# BMS-S04-V00-Microcontroller.net
KiCad netlist of a schematic drawn in Altium Designer
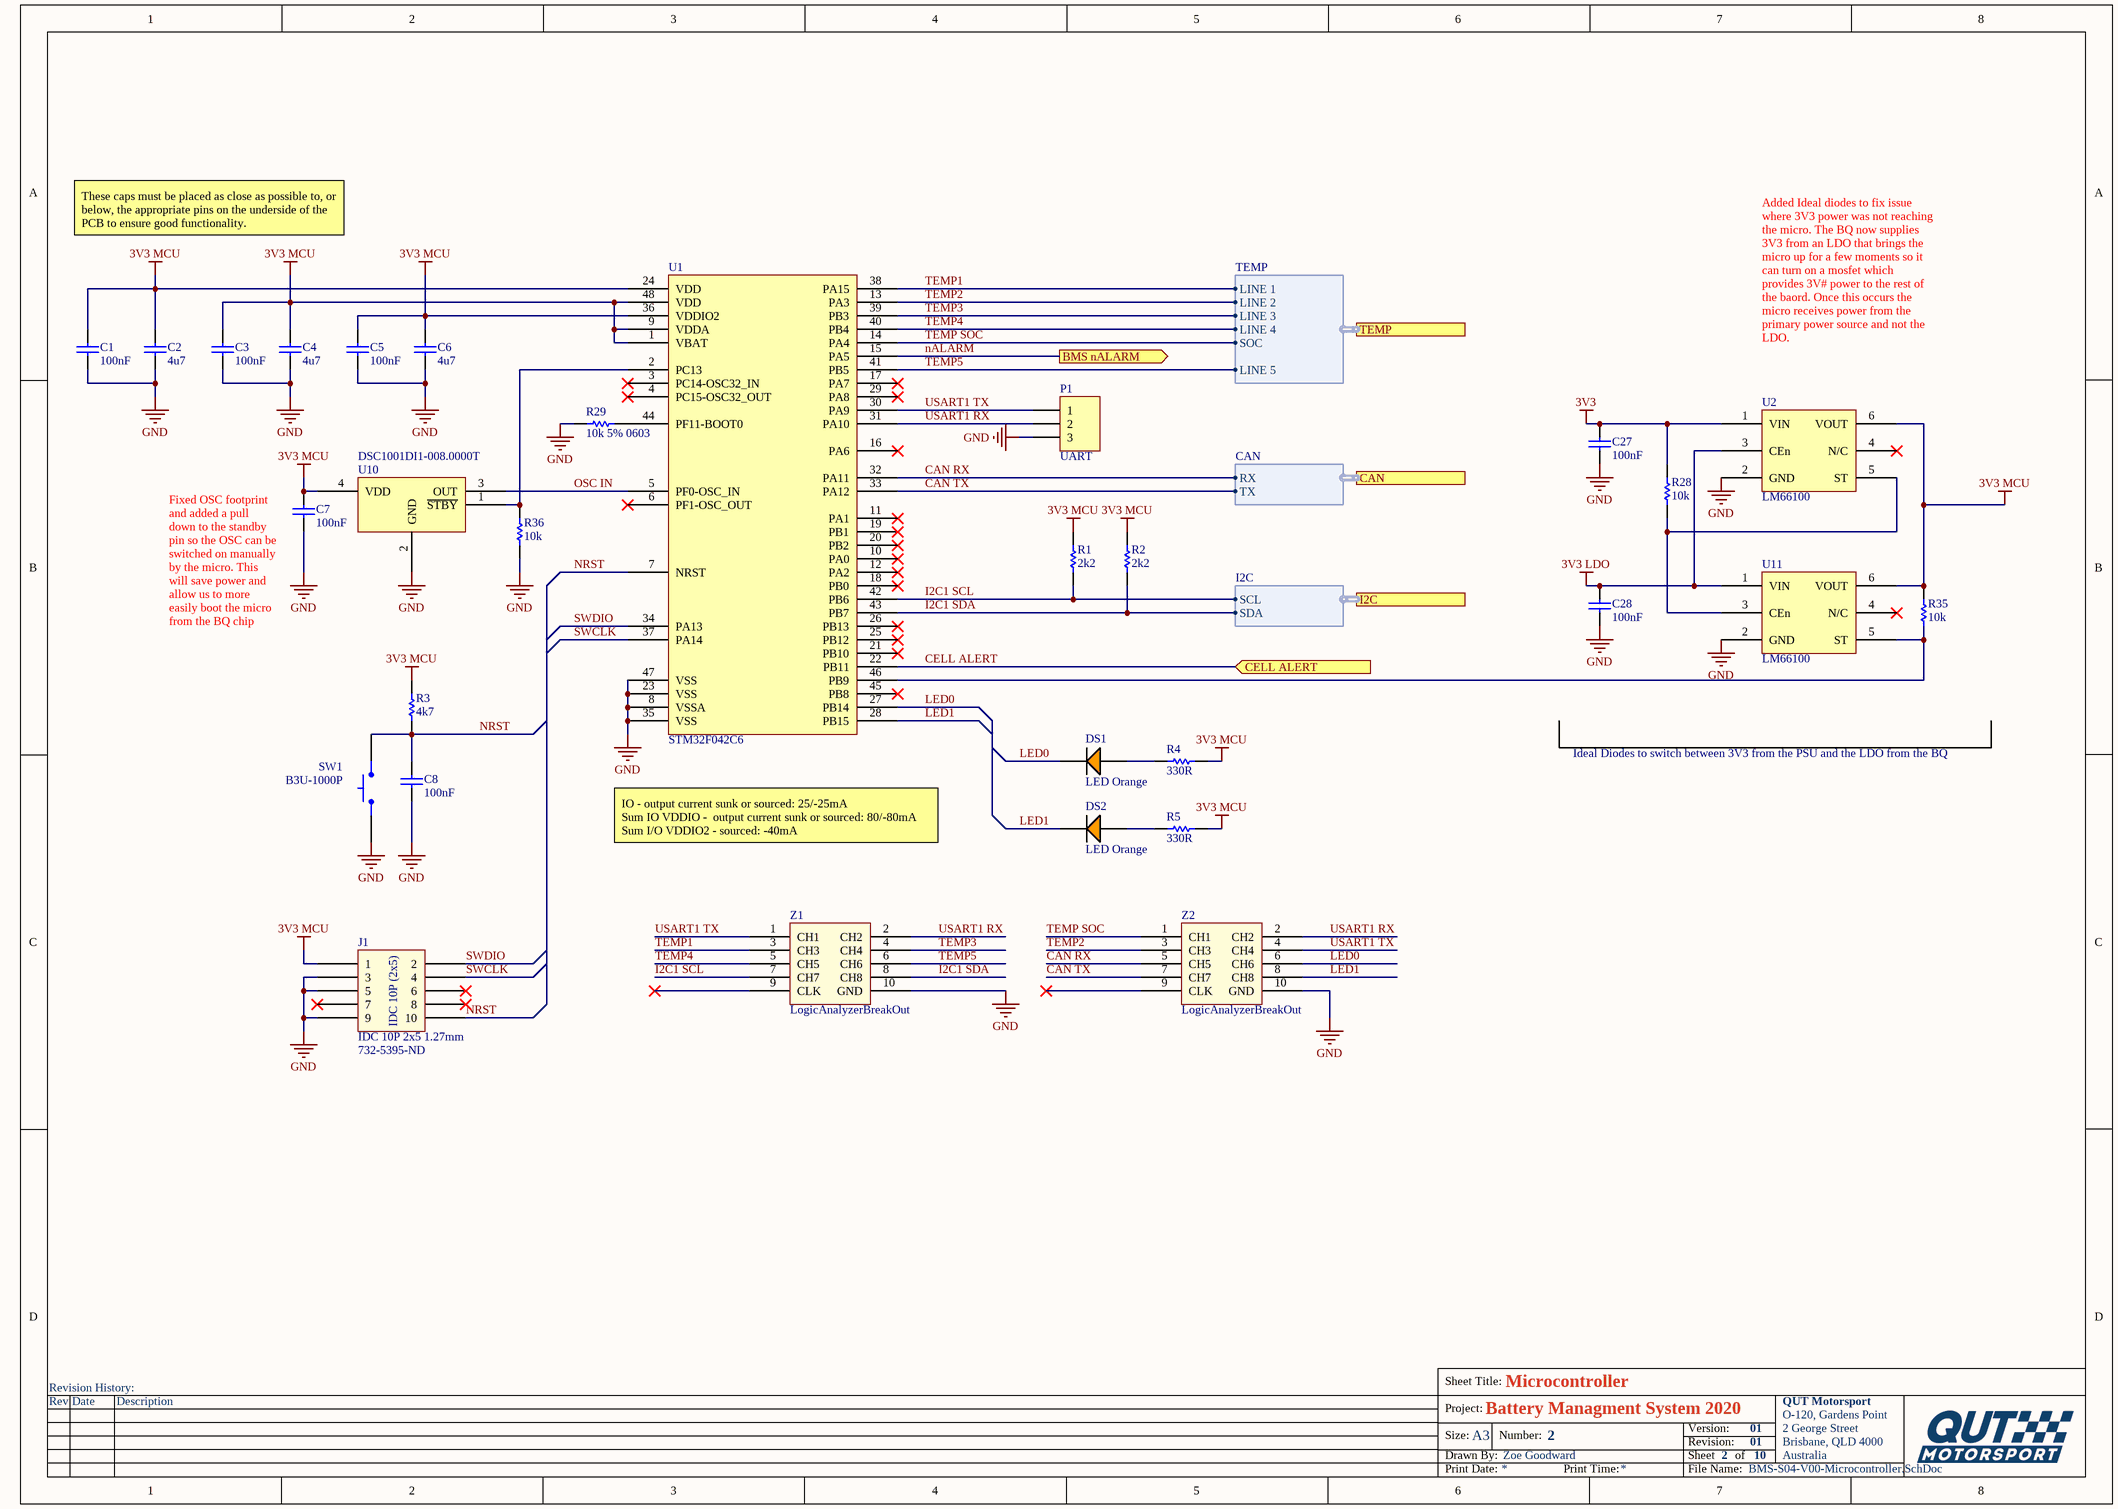
[diagram p0: BMS-S04-V00-Microcontroller.SchDoc]

(export (version "E")
  (design (tool "Eeschema 10.0.6"))
  (components
    (comp (ref "C1")
      (value "100nF")
      (footprint "Cap_Ceramic_0603")
      (description "Capacitor, Ceramic, SMD, 100nF, 50V, 5%, X7R, 0603")
      (libsource (lib "StandardCapacitors") (part "100nF 50V 5% X7R 0603"))
    )
    (comp (ref "C2")
      (value "4u7")
      (footprint "Cap_Ceramic_0603")
      (description "Capacitor, Ceramic, SMD, 4u7, 50V, 5%, X7R, 0603")
      (libsource (lib "StandardCapacitors") (part "4u7 50V 5% X7R 0603"))
    )
    (comp (ref "C3")
      (value "100nF")
      (footprint "Cap_Ceramic_0603")
      (description "Capacitor, Ceramic, SMD, 100nF, 50V, 5%, X7R, 0603")
      (libsource (lib "StandardCapacitors") (part "100nF 50V 5% X7R 0603"))
    )
    (comp (ref "C4")
      (value "4u7")
      (footprint "Cap_Ceramic_0603")
      (description "Capacitor, Ceramic, SMD, 4u7, 50V, 5%, X7R, 0603")
      (libsource (lib "StandardCapacitors") (part "4u7 50V 5% X7R 0603"))
    )
    (comp (ref "C5")
      (value "100nF")
      (footprint "Cap_Ceramic_0603")
      (description "Capacitor, Ceramic, SMD, 100nF, 50V, 5%, X7R, 0603")
      (libsource (lib "StandardCapacitors") (part "100nF 50V 5% X7R 0603"))
    )
    (comp (ref "C6")
      (value "4u7")
      (footprint "Cap_Ceramic_0603")
      (description "Capacitor, Ceramic, SMD, 4u7, 50V, 5%, X7R, 0603")
      (libsource (lib "StandardCapacitors") (part "4u7 50V 5% X7R 0603"))
    )
    (comp (ref "C7")
      (value "100nF")
      (footprint "Cap_Ceramic_0603")
      (description "Capacitor, Ceramic, SMD, 100nF, 50V, 5%, X7R, 0603")
      (libsource (lib "StandardCapacitors") (part "100nF 50V 5% X7R 0603"))
    )
    (comp (ref "C8")
      (value "100nF")
      (footprint "Cap_Ceramic_0603")
      (description "Capacitor, Ceramic, SMD, 100nF, 50V, 5%, X7R, 0603")
      (libsource (lib "StandardCapacitors") (part "100nF 50V 5% X7R 0603"))
    )
    (comp (ref "C27")
      (value "100nF")
      (footprint "Cap_Ceramic_0603")
      (description "Capacitor, Ceramic, SMD, 100nF, 50V, 5%, X7R, 0603")
      (libsource (lib "StandardCapacitors") (part "100nF 50V 5% X7R 0603"))
    )
    (comp (ref "C28")
      (value "100nF")
      (footprint "Cap_Ceramic_0603")
      (description "Capacitor, Ceramic, SMD, 100nF, 50V, 5%, X7R, 0603")
      (libsource (lib "StandardCapacitors") (part "100nF 50V 5% X7R 0603"))
    )
    (comp (ref "DS1")
      (value "LED Orange")
      (footprint "LED ORANGE 0603")
      (libsource (lib "QUTMS_LEDLibrary") (part "LED ORANGE 0603"))
    )
    (comp (ref "DS2")
      (value "LED Orange")
      (footprint "LED ORANGE 0603")
      (libsource (lib "QUTMS_LEDLibrary") (part "LED ORANGE 0603"))
    )
    (comp (ref "J1")
      (value "IDC 10P 2x5 1.27mm")
      (footprint "IDC 1.27MM 10P")
      (libsource (lib "IDCConnectors") (part "IDC 10P 2x5 1.27mm"))
    )
    (comp (ref "P1")
      (value "UART")
      (footprint "HDR1X3")
      (description "Header, 3-Pin")
      (fields (field (name "PUBLISHER") "Altium Limited"))
      (libsource (lib "Miscellaneous Connectors") (part "Header 3"))
    )
    (comp (ref "R1")
      (value "2k2")
      (footprint "Res_ThinFilm_0603")
      (description "Resistor, SMD, 2k2, 0.1W, 5%, 0603")
      (libsource (lib "StandardResistors") (part "2k2 5% 0603"))
    )
    (comp (ref "R2")
      (value "2k2")
      (footprint "Res_ThinFilm_0603")
      (description "Resistor, SMD, 2k2, 0.1W, 5%, 0603")
      (libsource (lib "StandardResistors") (part "2k2 5% 0603"))
    )
    (comp (ref "R3")
      (value "4k7")
      (footprint "Res_ThinFilm_0603")
      (description "Resistor, SMD, 4k7, 0.1W, 5%, 0603")
      (libsource (lib "StandardResistors") (part "4k7 5% 0603"))
    )
    (comp (ref "R4")
      (value "330R")
      (footprint "Res_ThinFilm_0603")
      (description "Resistor, SMD, 330R, 0.1W, 5%, 0603")
      (libsource (lib "StandardResistors") (part "330R 5% 0603"))
    )
    (comp (ref "R5")
      (value "330R")
      (footprint "Res_ThinFilm_0603")
      (description "Resistor, SMD, 330R, 0.1W, 5%, 0603")
      (libsource (lib "StandardResistors") (part "330R 5% 0603"))
    )
    (comp (ref "R28")
      (value "10k")
      (footprint "Res_ThinFilm_0603")
      (description "Resistor, SMD, 10k, 0.1W, 1%, 0603")
      (libsource (lib "StandardResistors") (part "10k 1% 0603"))
    )
    (comp (ref "R29")
      (value "10k 5% 0603")
      (footprint "Res_ThinFilm_0603")
      (description "Resistor, SMD, 10k, 0.1W, 5%, 0603")
      (libsource (lib "StandardResistors") (part "10k 5% 0603"))
    )
    (comp (ref "R35")
      (value "10k")
      (footprint "Res_ThinFilm_0603")
      (description "Resistor, SMD, 10k, 0.1W, 1%, 0603")
      (libsource (lib "StandardResistors") (part "10k 1% 0603"))
    )
    (comp (ref "R36")
      (value "10k")
      (footprint "Res_ThinFilm_0603")
      (description "Resistor, SMD, 10k, 0.1W, 5%, 0603")
      (libsource (lib "StandardResistors") (part "10k 5% 0603"))
    )
    (comp (ref "SW1")
      (value "B3U-1000P")
      (footprint "BTN B3U-1000P")
      (description "Omron B3U-1000P Ultra Miniture Switch")
      (libsource (lib "QUTMS_SwitchLibrary") (part "BTN B3U-1000P"))
    )
    (comp (ref "U1")
      (value "STM32F042C6")
      (footprint "STM32F042C6")
      (description "ARM® Cortex®-M0 STM32F0 Microcontroller IC 32-Bit 48MHz 32KB (32K x 8) FLASH 48-LQFP (7x7)")
      (libsource (lib "QUTMS_STM32Library") (part "STM32042C6"))
    )
    (comp (ref "U2")
      (value "LM66100")
      (footprint "LM66100")
      (description "Diode, SMD, 5.5V, 1.5A, SC-70")
      (fields
        (field (name "MANUFACTURER") "ON Semiconductor / Fairchild")
        (field (name "MANUFACTURER PART NUMBER") "1N914BWS")
      )
      (libsource (lib "QUTMS_DiodeLibrary") (part "LM66100"))
    )
    (comp (ref "U10")
      (value "DSC1001DI1-008.0000T")
      (footprint "DSC1001DI1-008.0000TCT-ND")
      (description "8MHz XO (Standard) CMOS Oscillator 1.8 ~ 3.3V Standby (Power Down) 4-SMD, No Lead")
      (libsource (lib "QUTMS_CrystalLibrary") (part "DSC1001DI1-008.0000T"))
    )
    (comp (ref "U11")
      (value "LM66100")
      (footprint "LM66100")
      (description "Diode, SMD, 5.5V, 1.5A, SC-70")
      (fields
        (field (name "MANUFACTURER") "ON Semiconductor / Fairchild")
        (field (name "MANUFACTURER PART NUMBER") "1N914BWS")
      )
      (libsource (lib "QUTMS_DiodeLibrary") (part "LM66100"))
    )
    (comp (ref "Z1")
      (value "LogicAnalyzerBreakOut")
      (footprint "LogicAnalyzer")
      (libsource (lib "StandardTest") (part "LogicAnalyer"))
    )
    (comp (ref "Z2")
      (value "LogicAnalyzerBreakOut")
      (footprint "LogicAnalyzer")
      (libsource (lib "StandardTest") (part "LogicAnalyer"))
    )
  )
  (nets
    (net (code "4") (name "/CAN RX") (class "Default")
      (node (ref "U1") (pin "32") (pinfunction "PA11_32") (pintype "passive"))
      (node (ref "Z2") (pin "5") (pinfunction "CH5_5") (pintype "passive"))
    )
    (net (code "5") (name "/CAN TX") (class "Default")
      (node (ref "U1") (pin "33") (pinfunction "PA12_33") (pintype "passive"))
      (node (ref "Z2") (pin "7") (pinfunction "CH7_7") (pintype "passive"))
    )
    (net (code "6") (name "/CELL ALERT") (class "Default")
      (node (ref "U1") (pin "22") (pinfunction "PB11_22") (pintype "passive"))
    )
    (net (code "7") (name "/I2C1 SCL") (class "Default")
      (node (ref "R1") (pin "1") (pinfunction "1_1") (pintype "passive"))
      (node (ref "U1") (pin "42") (pinfunction "PB6_42") (pintype "passive"))
      (node (ref "Z1") (pin "7") (pinfunction "CH7_7") (pintype "passive"))
    )
    (net (code "8") (name "/I2C1 SDA") (class "Default")
      (node (ref "R2") (pin "1") (pinfunction "1_1") (pintype "passive"))
      (node (ref "U1") (pin "43") (pinfunction "PB7_43") (pintype "passive"))
      (node (ref "Z1") (pin "8") (pinfunction "CH8_8") (pintype "passive"))
    )
    (net (code "9") (name "/LED0") (class "Default")
      (node (ref "DS1") (pin "2") (pinfunction "C_2") (pintype "passive"))
      (node (ref "U1") (pin "27") (pinfunction "PB14_27") (pintype "passive"))
      (node (ref "Z2") (pin "6") (pinfunction "CH6_6") (pintype "passive"))
    )
    (net (code "10") (name "/LED1") (class "Default")
      (node (ref "DS2") (pin "2") (pinfunction "C_2") (pintype "passive"))
      (node (ref "U1") (pin "28") (pinfunction "PB15_28") (pintype "passive"))
      (node (ref "Z2") (pin "8") (pinfunction "CH8_8") (pintype "passive"))
    )
    (net (code "11") (name "/NRST") (class "Default")
      (node (ref "C8") (pin "2") (pinfunction "2_2") (pintype "passive"))
      (node (ref "J1") (pin "10") (pinfunction "10_10") (pintype "passive"))
      (node (ref "R3") (pin "1") (pinfunction "1_1") (pintype "passive"))
      (node (ref "SW1") (pin "2") (pinfunction "2_2") (pintype "passive"))
      (node (ref "U1") (pin "7") (pinfunction "NRST_7") (pintype "passive"))
    )
    (net (code "12") (name "/OSC IN") (class "Default")
      (node (ref "U1") (pin "5") (pinfunction "PF0-OSC_IN_5") (pintype "passive"))
      (node (ref "U10") (pin "3") (pinfunction "OUT_3") (pintype "passive"))
    )
    (net (code "13") (name "/SWCLK") (class "Default")
      (node (ref "J1") (pin "4") (pinfunction "4_4") (pintype "passive"))
      (node (ref "U1") (pin "37") (pinfunction "PA14_37") (pintype "passive"))
    )
    (net (code "14") (name "/SWDIO") (class "Default")
      (node (ref "J1") (pin "2") (pinfunction "2_2") (pintype "passive"))
      (node (ref "U1") (pin "34") (pinfunction "PA13_34") (pintype "passive"))
    )
    (net (code "15") (name "/TEMP SOC") (class "Default")
      (node (ref "U1") (pin "14") (pinfunction "PA4_14") (pintype "passive"))
      (node (ref "Z2") (pin "1") (pinfunction "CH1_1") (pintype "passive"))
    )
    (net (code "16") (name "/TEMP1") (class "Default")
      (node (ref "U1") (pin "38") (pinfunction "PA15_38") (pintype "passive"))
      (node (ref "Z1") (pin "3") (pinfunction "CH3_3") (pintype "passive"))
    )
    (net (code "17") (name "/TEMP2") (class "Default")
      (node (ref "U1") (pin "13") (pinfunction "PA3_13") (pintype "passive"))
      (node (ref "Z2") (pin "3") (pinfunction "CH3_3") (pintype "passive"))
    )
    (net (code "18") (name "/TEMP3") (class "Default")
      (node (ref "U1") (pin "39") (pinfunction "PB3_39") (pintype "passive"))
      (node (ref "Z1") (pin "4") (pinfunction "CH4_4") (pintype "passive"))
    )
    (net (code "19") (name "/TEMP4") (class "Default")
      (node (ref "U1") (pin "40") (pinfunction "PB4_40") (pintype "passive"))
      (node (ref "Z1") (pin "5") (pinfunction "CH5_5") (pintype "passive"))
    )
    (net (code "20") (name "/TEMP5") (class "Default")
      (node (ref "U1") (pin "41") (pinfunction "PB5_41") (pintype "passive"))
      (node (ref "Z1") (pin "6") (pinfunction "CH6_6") (pintype "passive"))
    )
    (net (code "21") (name "/USART1 RX") (class "Default")
      (node (ref "P1") (pin "2") (pinfunction "2_2") (pintype "passive"))
      (node (ref "U1") (pin "31") (pinfunction "PA10_31") (pintype "passive"))
      (node (ref "Z1") (pin "2") (pinfunction "CH2_2") (pintype "passive"))
      (node (ref "Z2") (pin "2") (pinfunction "CH2_2") (pintype "passive"))
    )
    (net (code "22") (name "/USART1 TX") (class "Default")
      (node (ref "P1") (pin "1") (pinfunction "1_1") (pintype "passive"))
      (node (ref "U1") (pin "30") (pinfunction "PA9_30") (pintype "passive"))
      (node (ref "Z1") (pin "1") (pinfunction "CH1_1") (pintype "passive"))
      (node (ref "Z2") (pin "4") (pinfunction "CH4_4") (pintype "passive"))
    )
    (net (code "23") (name "/nALARM") (class "Default")
      (node (ref "U1") (pin "15") (pinfunction "PA5_15") (pintype "passive"))
    )
    (net (code "27") (name "3V3") (class "Default")
      (node (ref "C27") (pin "2") (pinfunction "2_2") (pintype "passive"))
      (node (ref "R28") (pin "2") (pinfunction "2_2") (pintype "passive"))
      (node (ref "U2") (pin "1") (pinfunction "VIN_1") (pintype "passive"))
    )
    (net (code "28") (name "3V3 LDO") (class "Default")
      (node (ref "C28") (pin "2") (pinfunction "2_2") (pintype "passive"))
      (node (ref "U11") (pin "1") (pinfunction "VIN_1") (pintype "passive"))
      (node (ref "U2") (pin "3") (pinfunction "CEn_3") (pintype "passive"))
    )
    (net (code "29") (name "3V3 MCU") (class "Default")
      (node (ref "C1") (pin "2") (pinfunction "2_2") (pintype "passive"))
      (node (ref "C2") (pin "2") (pinfunction "2_2") (pintype "passive"))
      (node (ref "C3") (pin "2") (pinfunction "2_2") (pintype "passive"))
      (node (ref "C4") (pin "2") (pinfunction "2_2") (pintype "passive"))
      (node (ref "C5") (pin "2") (pinfunction "2_2") (pintype "passive"))
      (node (ref "C6") (pin "2") (pinfunction "2_2") (pintype "passive"))
      (node (ref "C7") (pin "2") (pinfunction "2_2") (pintype "passive"))
      (node (ref "J1") (pin "1") (pinfunction "1_1") (pintype "passive"))
      (node (ref "R1") (pin "2") (pinfunction "2_2") (pintype "passive"))
      (node (ref "R2") (pin "2") (pinfunction "2_2") (pintype "passive"))
      (node (ref "R3") (pin "2") (pinfunction "2_2") (pintype "passive"))
      (node (ref "R35") (pin "2") (pinfunction "2_2") (pintype "passive"))
      (node (ref "R4") (pin "2") (pinfunction "2_2") (pintype "passive"))
      (node (ref "R5") (pin "2") (pinfunction "2_2") (pintype "passive"))
      (node (ref "U1") (pin "1") (pinfunction "VBAT_1") (pintype "passive"))
      (node (ref "U1") (pin "24") (pinfunction "VDD_24") (pintype "passive"))
      (node (ref "U1") (pin "36") (pinfunction "VDDIO2_36") (pintype "passive"))
      (node (ref "U1") (pin "48") (pinfunction "VDD_48") (pintype "passive"))
      (node (ref "U1") (pin "9") (pinfunction "VDDA_9") (pintype "passive"))
      (node (ref "U10") (pin "4") (pinfunction "VDD_4") (pintype "passive"))
      (node (ref "U11") (pin "6") (pinfunction "VOUT_6") (pintype "passive"))
      (node (ref "U2") (pin "6") (pinfunction "VOUT_6") (pintype "passive"))
    )
    (net (code "30") (name "GND") (class "Default")
      (node (ref "C1") (pin "1") (pinfunction "1_1") (pintype "passive"))
      (node (ref "C2") (pin "1") (pinfunction "1_1") (pintype "passive"))
      (node (ref "C27") (pin "1") (pinfunction "1_1") (pintype "passive"))
      (node (ref "C28") (pin "1") (pinfunction "1_1") (pintype "passive"))
      (node (ref "C3") (pin "1") (pinfunction "1_1") (pintype "passive"))
      (node (ref "C4") (pin "1") (pinfunction "1_1") (pintype "passive"))
      (node (ref "C5") (pin "1") (pinfunction "1_1") (pintype "passive"))
      (node (ref "C6") (pin "1") (pinfunction "1_1") (pintype "passive"))
      (node (ref "C7") (pin "1") (pinfunction "1_1") (pintype "passive"))
      (node (ref "C8") (pin "1") (pinfunction "1_1") (pintype "passive"))
      (node (ref "J1") (pin "3") (pinfunction "3_3") (pintype "passive"))
      (node (ref "J1") (pin "5") (pinfunction "5_5") (pintype "passive"))
      (node (ref "J1") (pin "9") (pinfunction "9_9") (pintype "passive"))
      (node (ref "P1") (pin "3") (pinfunction "3_3") (pintype "passive"))
      (node (ref "R29") (pin "1") (pinfunction "1_1") (pintype "passive"))
      (node (ref "R36") (pin "1") (pinfunction "1_1") (pintype "passive"))
      (node (ref "SW1") (pin "1") (pinfunction "1_1") (pintype "passive"))
      (node (ref "U1") (pin "23") (pinfunction "VSS_23") (pintype "passive"))
      (node (ref "U1") (pin "35") (pinfunction "VSS_35") (pintype "passive"))
      (node (ref "U1") (pin "47") (pinfunction "VSS_47") (pintype "passive"))
      (node (ref "U1") (pin "8") (pinfunction "VSSA_8") (pintype "passive"))
      (node (ref "U10") (pin "2") (pinfunction "GND_2") (pintype "passive"))
      (node (ref "U11") (pin "2") (pinfunction "GND_2") (pintype "passive"))
      (node (ref "U2") (pin "2") (pinfunction "GND_2") (pintype "passive"))
      (node (ref "Z1") (pin "10") (pinfunction "GND_10") (pintype "passive"))
      (node (ref "Z2") (pin "10") (pinfunction "GND_10") (pintype "passive"))
    )
    (net (code "31") (name "Net-(DS1-A)") (class "Default")
      (node (ref "DS1") (pin "1") (pinfunction "A_1") (pintype "passive"))
      (node (ref "R4") (pin "1") (pinfunction "1_1") (pintype "passive"))
    )
    (net (code "32") (name "Net-(DS2-A)") (class "Default")
      (node (ref "DS2") (pin "1") (pinfunction "A_1") (pintype "passive"))
      (node (ref "R5") (pin "1") (pinfunction "1_1") (pintype "passive"))
    )
    (net (code "33") (name "Net-(U1-PB9)") (class "Default")
      (node (ref "R35") (pin "1") (pinfunction "1_1") (pintype "passive"))
      (node (ref "U1") (pin "46") (pinfunction "PB9_46") (pintype "passive"))
      (node (ref "U11") (pin "5") (pinfunction "ST_5") (pintype "passive"))
    )
    (net (code "34") (name "Net-(U1-PC13)") (class "Default")
      (node (ref "R36") (pin "2") (pinfunction "2_2") (pintype "passive"))
      (node (ref "U1") (pin "2") (pinfunction "PC13_2") (pintype "passive"))
      (node (ref "U10") (pin "1") (pinfunction "~{STBY}_1") (pintype "passive"))
    )
    (net (code "35") (name "Net-(U1-PF11-BOOT0)") (class "Default")
      (node (ref "R29") (pin "2") (pinfunction "2_2") (pintype "passive"))
      (node (ref "U1") (pin "44") (pinfunction "PF11-BOOT0_44") (pintype "passive"))
    )
    (net (code "36") (name "Net-(U11-CEn)") (class "Default")
      (node (ref "R28") (pin "1") (pinfunction "1_1") (pintype "passive"))
      (node (ref "U11") (pin "3") (pinfunction "CEn_3") (pintype "passive"))
      (node (ref "U2") (pin "5") (pinfunction "ST_5") (pintype "passive"))
    )
    (net (code "37") (name "unconnected-(J1-Pad6)") (class "Default")
      (node (ref "J1") (pin "6") (pinfunction "6_6") (pintype "passive+no_connect"))
    )
    (net (code "38") (name "unconnected-(J1-Pad7)") (class "Default")
      (node (ref "J1") (pin "7") (pinfunction "7_7") (pintype "passive+no_connect"))
    )
    (net (code "39") (name "unconnected-(J1-Pad8)") (class "Default")
      (node (ref "J1") (pin "8") (pinfunction "8_8") (pintype "passive+no_connect"))
    )
    (net (code "40") (name "unconnected-(U1-PA0-Pad10)") (class "Default")
      (node (ref "U1") (pin "10") (pinfunction "PA0_10") (pintype "passive+no_connect"))
    )
    (net (code "41") (name "unconnected-(U1-PA1-Pad11)") (class "Default")
      (node (ref "U1") (pin "11") (pinfunction "PA1_11") (pintype "passive+no_connect"))
    )
    (net (code "42") (name "unconnected-(U1-PA2-Pad12)") (class "Default")
      (node (ref "U1") (pin "12") (pinfunction "PA2_12") (pintype "passive+no_connect"))
    )
    (net (code "43") (name "unconnected-(U1-PA6-Pad16)") (class "Default")
      (node (ref "U1") (pin "16") (pinfunction "PA6_16") (pintype "passive+no_connect"))
    )
    (net (code "44") (name "unconnected-(U1-PA7-Pad17)") (class "Default")
      (node (ref "U1") (pin "17") (pinfunction "PA7_17") (pintype "passive+no_connect"))
    )
    (net (code "45") (name "unconnected-(U1-PA8-Pad29)") (class "Default")
      (node (ref "U1") (pin "29") (pinfunction "PA8_29") (pintype "passive+no_connect"))
    )
    (net (code "46") (name "unconnected-(U1-PB0-Pad18)") (class "Default")
      (node (ref "U1") (pin "18") (pinfunction "PB0_18") (pintype "passive+no_connect"))
    )
    (net (code "47") (name "unconnected-(U1-PB1-Pad19)") (class "Default")
      (node (ref "U1") (pin "19") (pinfunction "PB1_19") (pintype "passive+no_connect"))
    )
    (net (code "48") (name "unconnected-(U1-PB2-Pad20)") (class "Default")
      (node (ref "U1") (pin "20") (pinfunction "PB2_20") (pintype "passive+no_connect"))
    )
    (net (code "49") (name "unconnected-(U1-PB8-Pad45)") (class "Default")
      (node (ref "U1") (pin "45") (pinfunction "PB8_45") (pintype "passive+no_connect"))
    )
    (net (code "50") (name "unconnected-(U1-PB10-Pad21)") (class "Default")
      (node (ref "U1") (pin "21") (pinfunction "PB10_21") (pintype "passive+no_connect"))
    )
    (net (code "51") (name "unconnected-(U1-PB12-Pad25)") (class "Default")
      (node (ref "U1") (pin "25") (pinfunction "PB12_25") (pintype "passive+no_connect"))
    )
    (net (code "52") (name "unconnected-(U1-PB13-Pad26)") (class "Default")
      (node (ref "U1") (pin "26") (pinfunction "PB13_26") (pintype "passive+no_connect"))
    )
    (net (code "53") (name "unconnected-(U1-PC14-OSC32_IN-Pad3)") (class "Default")
      (node (ref "U1") (pin "3") (pinfunction "PC14-OSC32_IN_3") (pintype "passive+no_connect"))
    )
    (net (code "54") (name "unconnected-(U1-PC15-OSC32_OUT-Pad4)") (class "Default")
      (node (ref "U1") (pin "4") (pinfunction "PC15-OSC32_OUT_4") (pintype "passive+no_connect"))
    )
    (net (code "55") (name "unconnected-(U1-PF1-OSC_OUT-Pad6)") (class "Default")
      (node (ref "U1") (pin "6") (pinfunction "PF1-OSC_OUT_6") (pintype "passive+no_connect"))
    )
    (net (code "56") (name "unconnected-(U2-N{slash}C-Pad4)") (class "Default")
      (node (ref "U2") (pin "4") (pinfunction "N/C_4") (pintype "passive+no_connect"))
    )
    (net (code "57") (name "unconnected-(U11-N{slash}C-Pad4)") (class "Default")
      (node (ref "U11") (pin "4") (pinfunction "N/C_4") (pintype "passive+no_connect"))
    )
    (net (code "58") (name "unconnected-(Z1-CLK-Pad9)") (class "Default")
      (node (ref "Z1") (pin "9") (pinfunction "CLK_9") (pintype "passive+no_connect"))
    )
    (net (code "59") (name "unconnected-(Z2-CLK-Pad9)") (class "Default")
      (node (ref "Z2") (pin "9") (pinfunction "CLK_9") (pintype "passive+no_connect"))
    )
  )
)
